# wordClock.net
KiCad netlist of a schematic drawn in EAGLE
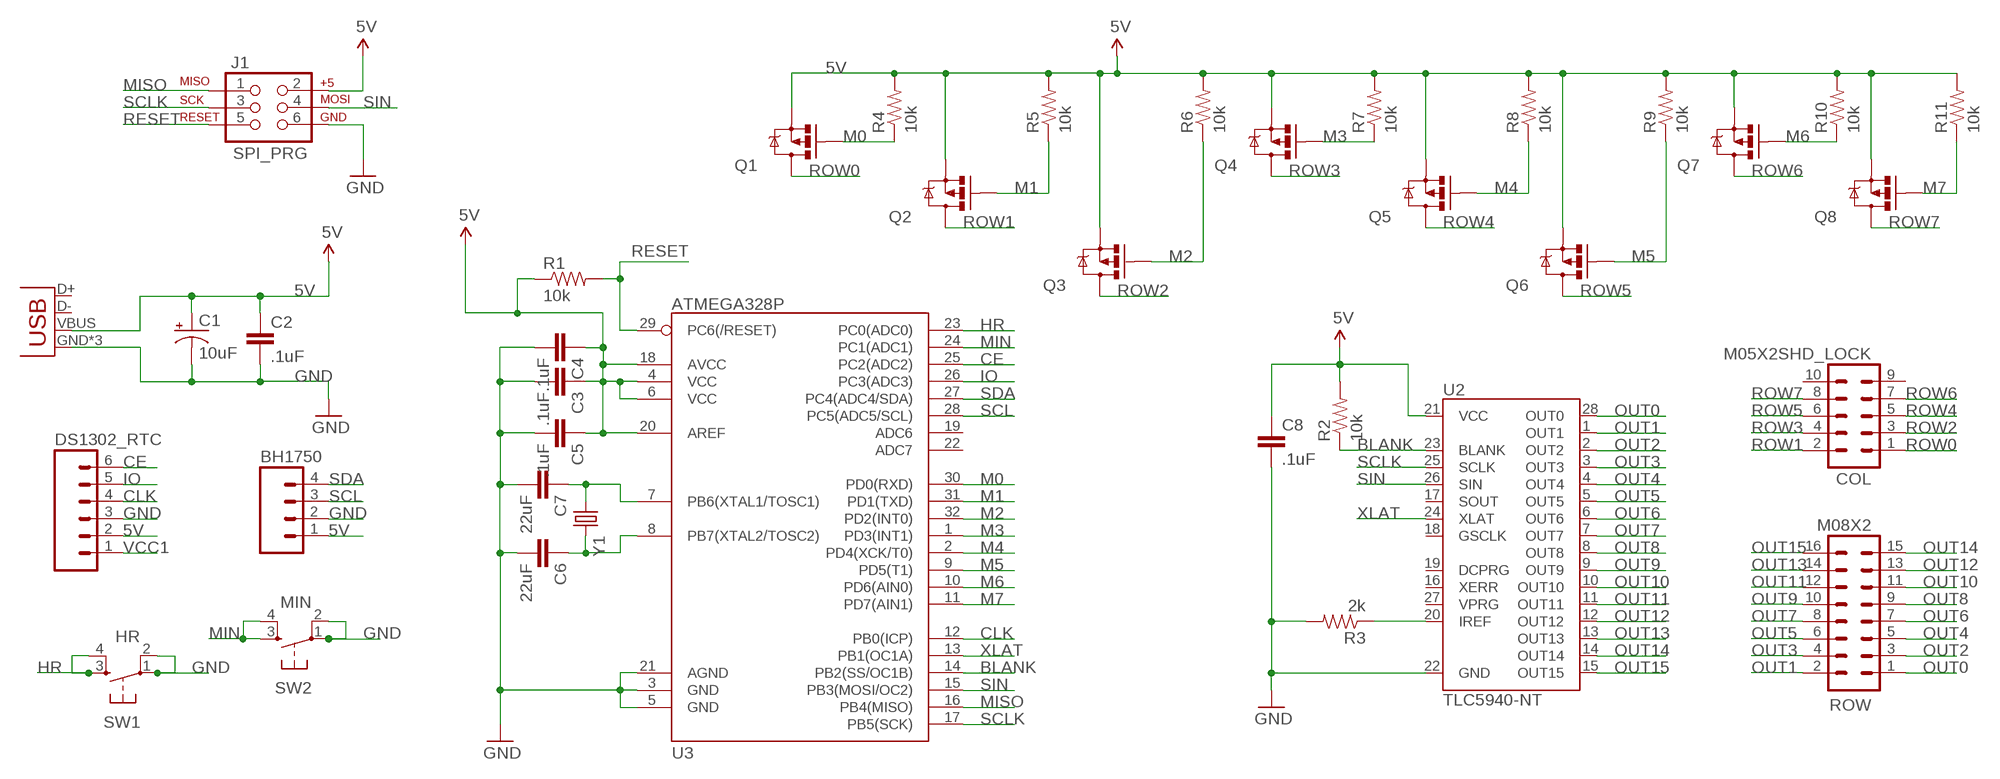
[diagram p0: schematic, sheet 1]

(export (version "E")
  (design (tool "Eeschema 10.0.6"))
  (components
    (comp (ref "BH1750")
      (value "M04LOCK")
      (footprint "eagle-import:1X04_LOCK")
      (libsource (lib "eagle-import") (part "M04LOCK"))
    )
    (comp (ref "C1")
      (value "10uF")
      (footprint "eagle-import:PANASONIC_D")
      (libsource (lib "eagle-import") (part "CAP_POLD"))
    )
    (comp (ref "C2")
      (value ".1uF")
      (footprint "eagle-import:0805")
      (libsource (lib "eagle-import") (part "CAP0805"))
    )
    (comp (ref "C3")
      (value ".1uF")
      (footprint "eagle-import:0805")
      (libsource (lib "eagle-import") (part "CAP0805"))
    )
    (comp (ref "C4")
      (value ".1uF")
      (footprint "eagle-import:0805")
      (libsource (lib "eagle-import") (part "CAP0805"))
    )
    (comp (ref "C5")
      (value ".1uF")
      (footprint "eagle-import:0805")
      (libsource (lib "eagle-import") (part "CAP0805"))
    )
    (comp (ref "C6")
      (value "22uF")
      (footprint "eagle-import:0805")
      (libsource (lib "eagle-import") (part "CAP0805"))
    )
    (comp (ref "C7")
      (value "22uF")
      (footprint "eagle-import:0805")
      (libsource (lib "eagle-import") (part "CAP0805"))
    )
    (comp (ref "C8")
      (value ".1uF")
      (footprint "eagle-import:0805")
      (libsource (lib "eagle-import") (part "CAP0805"))
    )
    (comp (ref "COL")
      (value "M05X2SHD_LOCK")
      (footprint "eagle-import:2X5-SHROUDED_LOCK")
      (libsource (lib "eagle-import") (part "M05X2SHD_LOCK"))
    )
    (comp (ref "DS1302_RTC")
      (value "M06FEMALE_LOCK")
      (footprint "eagle-import:1X06_FEMALE_LOCK.010")
      (libsource (lib "eagle-import") (part "M06FEMALE_LOCK"))
    )
    (comp (ref "J1")
      (value "SPI_PRG")
      (footprint "eagle-import:2X3_LOCK")
      (libsource (lib "eagle-import") (part "AVR_SPI_PRG_62X3_LOCK"))
    )
    (comp (ref "JP1")
      (value "USB-MICROB")
      (footprint "eagle-import:USB-MICROB")
      (libsource (lib "eagle-import") (part "USB-MICROB"))
    )
    (comp (ref "Q1")
      (value "MOSFET-PCHANNELSMD")
      (footprint "eagle-import:SOT23-3")
      (libsource (lib "eagle-import") (part "MOSFET-PCHANNELSMD"))
    )
    (comp (ref "Q2")
      (value "MOSFET-PCHANNELSMD")
      (footprint "eagle-import:SOT23-3")
      (libsource (lib "eagle-import") (part "MOSFET-PCHANNELSMD"))
    )
    (comp (ref "Q3")
      (value "MOSFET-PCHANNELSMD")
      (footprint "eagle-import:SOT23-3")
      (libsource (lib "eagle-import") (part "MOSFET-PCHANNELSMD"))
    )
    (comp (ref "Q4")
      (value "MOSFET-PCHANNELSMD")
      (footprint "eagle-import:SOT23-3")
      (libsource (lib "eagle-import") (part "MOSFET-PCHANNELSMD"))
    )
    (comp (ref "Q5")
      (value "MOSFET-PCHANNELSMD")
      (footprint "eagle-import:SOT23-3")
      (libsource (lib "eagle-import") (part "MOSFET-PCHANNELSMD"))
    )
    (comp (ref "Q6")
      (value "MOSFET-PCHANNELSMD")
      (footprint "eagle-import:SOT23-3")
      (libsource (lib "eagle-import") (part "MOSFET-PCHANNELSMD"))
    )
    (comp (ref "Q7")
      (value "MOSFET-PCHANNELSMD")
      (footprint "eagle-import:SOT23-3")
      (libsource (lib "eagle-import") (part "MOSFET-PCHANNELSMD"))
    )
    (comp (ref "Q8")
      (value "MOSFET-PCHANNELSMD")
      (footprint "eagle-import:SOT23-3")
      (libsource (lib "eagle-import") (part "MOSFET-PCHANNELSMD"))
    )
    (comp (ref "R1")
      (value "10k")
      (footprint "eagle-import:0805")
      (libsource (lib "eagle-import") (part "RESISTOR0805-RES"))
    )
    (comp (ref "R2")
      (value "10k")
      (footprint "eagle-import:0805")
      (libsource (lib "eagle-import") (part "RESISTOR0805-RES"))
    )
    (comp (ref "R3")
      (value "2k")
      (footprint "eagle-import:0805")
      (libsource (lib "eagle-import") (part "RESISTOR0805-RES"))
    )
    (comp (ref "R4")
      (value "10k")
      (footprint "eagle-import:0805")
      (libsource (lib "eagle-import") (part "RESISTOR0805-RES"))
    )
    (comp (ref "R5")
      (value "10k")
      (footprint "eagle-import:0805")
      (libsource (lib "eagle-import") (part "RESISTOR0805-RES"))
    )
    (comp (ref "R6")
      (value "10k")
      (footprint "eagle-import:0805")
      (libsource (lib "eagle-import") (part "RESISTOR0805-RES"))
    )
    (comp (ref "R7")
      (value "10k")
      (footprint "eagle-import:0805")
      (libsource (lib "eagle-import") (part "RESISTOR0805-RES"))
    )
    (comp (ref "R8")
      (value "10k")
      (footprint "eagle-import:0805")
      (libsource (lib "eagle-import") (part "RESISTOR0805-RES"))
    )
    (comp (ref "R9")
      (value "10k")
      (footprint "eagle-import:0805")
      (libsource (lib "eagle-import") (part "RESISTOR0805-RES"))
    )
    (comp (ref "R10")
      (value "10k")
      (footprint "eagle-import:0805")
      (libsource (lib "eagle-import") (part "RESISTOR0805-RES"))
    )
    (comp (ref "R11")
      (value "10k")
      (footprint "eagle-import:0805")
      (libsource (lib "eagle-import") (part "RESISTOR0805-RES"))
    )
    (comp (ref "ROW")
      (value "M08X2")
      (footprint "eagle-import:2X8")
      (libsource (lib "eagle-import") (part "M08X2"))
    )
    (comp (ref "SW1")
      (value "HR")
      (footprint "eagle-import:TACTILE-PTH")
      (libsource (lib "eagle-import") (part "TAC_SWITCHPTH"))
    )
    (comp (ref "SW2")
      (value "MIN")
      (footprint "eagle-import:TACTILE-PTH")
      (libsource (lib "eagle-import") (part "TAC_SWITCHPTH"))
    )
    (comp (ref "U2")
      (value "TLC5940-NT")
      (footprint "eagle-import:DIL28-3")
      (libsource (lib "eagle-import") (part "TLC5940-NT"))
    )
    (comp (ref "U3")
      (value "ATMEGA328P")
      (footprint "eagle-import:TQFP32-08")
      (libsource (lib "eagle-import") (part "ATMEGA328_SMT"))
    )
    (comp (ref "Y1")
      (value "CRYSTALHC49UV")
      (footprint "eagle-import:HC49U-V")
      (libsource (lib "eagle-import") (part "CRYSTALHC49UV"))
    )
  )
  (nets
    (net (code "1") (name "/BLANK") (class "Default")
      (node (ref "R2") (pin "1") (pinfunction "1_1") (pintype "passive"))
      (node (ref "U2") (pin "23") (pinfunction "BLANK_23") (pintype "bidirectional"))
      (node (ref "U3") (pin "14") (pinfunction "PB2(SS/OC1B)_14") (pintype "bidirectional"))
    )
    (net (code "2") (name "/CE") (class "Default")
      (node (ref "DS1302_RTC") (pin "6") (pinfunction "6_6") (pintype "passive"))
      (node (ref "U3") (pin "25") (pinfunction "PC2(ADC2)_25") (pintype "bidirectional"))
    )
    (net (code "3") (name "/CLK") (class "Default")
      (node (ref "DS1302_RTC") (pin "4") (pinfunction "4_4") (pintype "passive"))
      (node (ref "U3") (pin "12") (pinfunction "PB0(ICP)_12") (pintype "bidirectional"))
    )
    (net (code "4") (name "/HR") (class "Default")
      (node (ref "SW1") (pin "3") (pinfunction "3_3") (pintype "passive"))
      (node (ref "SW1") (pin "4") (pinfunction "4_4") (pintype "passive"))
      (node (ref "U3") (pin "23") (pinfunction "PC0(ADC0)_23") (pintype "bidirectional"))
    )
    (net (code "5") (name "/IO") (class "Default")
      (node (ref "DS1302_RTC") (pin "5") (pinfunction "5_5") (pintype "passive"))
      (node (ref "U3") (pin "26") (pinfunction "PC3(ADC3)_26") (pintype "bidirectional"))
    )
    (net (code "6") (name "/M0") (class "Default")
      (node (ref "Q1") (pin "1") (pinfunction "G_1") (pintype "passive"))
      (node (ref "R4") (pin "1") (pinfunction "1_1") (pintype "passive"))
      (node (ref "U3") (pin "30") (pinfunction "PD0(RXD)_30") (pintype "bidirectional"))
    )
    (net (code "7") (name "/M1") (class "Default")
      (node (ref "Q2") (pin "1") (pinfunction "G_1") (pintype "passive"))
      (node (ref "R5") (pin "1") (pinfunction "1_1") (pintype "passive"))
      (node (ref "U3") (pin "31") (pinfunction "PD1(TXD)_31") (pintype "bidirectional"))
    )
    (net (code "8") (name "/M2") (class "Default")
      (node (ref "Q3") (pin "1") (pinfunction "G_1") (pintype "passive"))
      (node (ref "R6") (pin "1") (pinfunction "1_1") (pintype "passive"))
      (node (ref "U3") (pin "32") (pinfunction "PD2(INT0)_32") (pintype "bidirectional"))
    )
    (net (code "9") (name "/M3") (class "Default")
      (node (ref "Q4") (pin "1") (pinfunction "G_1") (pintype "passive"))
      (node (ref "R7") (pin "1") (pinfunction "1_1") (pintype "passive"))
      (node (ref "U3") (pin "1") (pinfunction "PD3(INT1)_1") (pintype "bidirectional"))
    )
    (net (code "10") (name "/M4") (class "Default")
      (node (ref "Q5") (pin "1") (pinfunction "G_1") (pintype "passive"))
      (node (ref "R8") (pin "1") (pinfunction "1_1") (pintype "passive"))
      (node (ref "U3") (pin "2") (pinfunction "PD4(XCK/T0)_2") (pintype "bidirectional"))
    )
    (net (code "11") (name "/M5") (class "Default")
      (node (ref "Q6") (pin "1") (pinfunction "G_1") (pintype "passive"))
      (node (ref "R9") (pin "1") (pinfunction "1_1") (pintype "passive"))
      (node (ref "U3") (pin "9") (pinfunction "PD5(T1)_9") (pintype "bidirectional"))
    )
    (net (code "12") (name "/M6") (class "Default")
      (node (ref "Q7") (pin "1") (pinfunction "G_1") (pintype "passive"))
      (node (ref "R10") (pin "1") (pinfunction "1_1") (pintype "passive"))
      (node (ref "U3") (pin "10") (pinfunction "PD6(AIN0)_10") (pintype "bidirectional"))
    )
    (net (code "13") (name "/M7") (class "Default")
      (node (ref "Q8") (pin "1") (pinfunction "G_1") (pintype "passive"))
      (node (ref "R11") (pin "1") (pinfunction "1_1") (pintype "passive"))
      (node (ref "U3") (pin "11") (pinfunction "PD7(AIN1)_11") (pintype "bidirectional"))
    )
    (net (code "14") (name "/MIN") (class "Default")
      (node (ref "SW2") (pin "3") (pinfunction "3_3") (pintype "passive"))
      (node (ref "SW2") (pin "4") (pinfunction "4_4") (pintype "passive"))
      (node (ref "U3") (pin "24") (pinfunction "PC1(ADC1)_24") (pintype "bidirectional"))
    )
    (net (code "15") (name "/MISO") (class "Default")
      (node (ref "J1") (pin "1") (pinfunction "1_1") (pintype "passive"))
      (node (ref "U3") (pin "16") (pinfunction "PB4(MISO)_16") (pintype "bidirectional"))
    )
    (net (code "16") (name "/OUT0") (class "Default")
      (node (ref "ROW") (pin "1") (pinfunction "1_1") (pintype "passive"))
      (node (ref "U2") (pin "28") (pinfunction "OUT0_28") (pintype "bidirectional"))
    )
    (net (code "17") (name "/OUT1") (class "Default")
      (node (ref "ROW") (pin "2") (pinfunction "2_2") (pintype "passive"))
      (node (ref "U2") (pin "1") (pinfunction "OUT1_1") (pintype "bidirectional"))
    )
    (net (code "18") (name "/OUT2") (class "Default")
      (node (ref "ROW") (pin "3") (pinfunction "3_3") (pintype "passive"))
      (node (ref "U2") (pin "2") (pinfunction "OUT2_2") (pintype "bidirectional"))
    )
    (net (code "19") (name "/OUT3") (class "Default")
      (node (ref "ROW") (pin "4") (pinfunction "4_4") (pintype "passive"))
      (node (ref "U2") (pin "3") (pinfunction "OUT3_3") (pintype "bidirectional"))
    )
    (net (code "20") (name "/OUT4") (class "Default")
      (node (ref "ROW") (pin "5") (pinfunction "5_5") (pintype "passive"))
      (node (ref "U2") (pin "4") (pinfunction "OUT4_4") (pintype "bidirectional"))
    )
    (net (code "21") (name "/OUT5") (class "Default")
      (node (ref "ROW") (pin "6") (pinfunction "6_6") (pintype "passive"))
      (node (ref "U2") (pin "5") (pinfunction "OUT5_5") (pintype "bidirectional"))
    )
    (net (code "22") (name "/OUT6") (class "Default")
      (node (ref "ROW") (pin "7") (pinfunction "7_7") (pintype "passive"))
      (node (ref "U2") (pin "6") (pinfunction "OUT6_6") (pintype "bidirectional"))
    )
    (net (code "23") (name "/OUT7") (class "Default")
      (node (ref "ROW") (pin "8") (pinfunction "8_8") (pintype "passive"))
      (node (ref "U2") (pin "7") (pinfunction "OUT7_7") (pintype "bidirectional"))
    )
    (net (code "24") (name "/OUT8") (class "Default")
      (node (ref "ROW") (pin "9") (pinfunction "9_9") (pintype "passive"))
      (node (ref "U2") (pin "8") (pinfunction "OUT8_8") (pintype "bidirectional"))
    )
    (net (code "25") (name "/OUT9") (class "Default")
      (node (ref "ROW") (pin "10") (pinfunction "10_10") (pintype "passive"))
      (node (ref "U2") (pin "9") (pinfunction "OUT9_9") (pintype "bidirectional"))
    )
    (net (code "26") (name "/OUT10") (class "Default")
      (node (ref "ROW") (pin "11") (pinfunction "11_11") (pintype "passive"))
      (node (ref "U2") (pin "10") (pinfunction "OUT10_10") (pintype "bidirectional"))
    )
    (net (code "27") (name "/OUT11") (class "Default")
      (node (ref "ROW") (pin "12") (pinfunction "12_12") (pintype "passive"))
      (node (ref "U2") (pin "11") (pinfunction "OUT11_11") (pintype "bidirectional"))
    )
    (net (code "28") (name "/OUT12") (class "Default")
      (node (ref "ROW") (pin "13") (pinfunction "13_13") (pintype "passive"))
      (node (ref "U2") (pin "12") (pinfunction "OUT12_12") (pintype "bidirectional"))
    )
    (net (code "29") (name "/OUT13") (class "Default")
      (node (ref "ROW") (pin "14") (pinfunction "14_14") (pintype "passive"))
      (node (ref "U2") (pin "13") (pinfunction "OUT13_13") (pintype "bidirectional"))
    )
    (net (code "30") (name "/OUT14") (class "Default")
      (node (ref "ROW") (pin "15") (pinfunction "15_15") (pintype "passive"))
      (node (ref "U2") (pin "14") (pinfunction "OUT14_14") (pintype "bidirectional"))
    )
    (net (code "31") (name "/OUT15") (class "Default")
      (node (ref "ROW") (pin "16") (pinfunction "16_16") (pintype "passive"))
      (node (ref "U2") (pin "15") (pinfunction "OUT15_15") (pintype "bidirectional"))
    )
    (net (code "32") (name "/RESET") (class "Default")
      (node (ref "J1") (pin "5") (pinfunction "5_5") (pintype "passive"))
      (node (ref "R1") (pin "2") (pinfunction "2_2") (pintype "passive"))
      (node (ref "U3") (pin "29") (pinfunction "PC6(/RESET)_29") (pintype "bidirectional"))
    )
    (net (code "33") (name "/ROW0") (class "Default")
      (node (ref "COL") (pin "1") (pinfunction "1_1") (pintype "passive"))
      (node (ref "Q1") (pin "3") (pinfunction "D_3") (pintype "passive"))
    )
    (net (code "34") (name "/ROW1") (class "Default")
      (node (ref "COL") (pin "2") (pinfunction "2_2") (pintype "passive"))
      (node (ref "Q2") (pin "3") (pinfunction "D_3") (pintype "passive"))
    )
    (net (code "35") (name "/ROW2") (class "Default")
      (node (ref "COL") (pin "3") (pinfunction "3_3") (pintype "passive"))
      (node (ref "Q3") (pin "3") (pinfunction "D_3") (pintype "passive"))
    )
    (net (code "36") (name "/ROW3") (class "Default")
      (node (ref "COL") (pin "4") (pinfunction "4_4") (pintype "passive"))
      (node (ref "Q4") (pin "3") (pinfunction "D_3") (pintype "passive"))
    )
    (net (code "37") (name "/ROW4") (class "Default")
      (node (ref "COL") (pin "5") (pinfunction "5_5") (pintype "passive"))
      (node (ref "Q5") (pin "3") (pinfunction "D_3") (pintype "passive"))
    )
    (net (code "38") (name "/ROW5") (class "Default")
      (node (ref "COL") (pin "6") (pinfunction "6_6") (pintype "passive"))
      (node (ref "Q6") (pin "3") (pinfunction "D_3") (pintype "passive"))
    )
    (net (code "39") (name "/ROW6") (class "Default")
      (node (ref "COL") (pin "7") (pinfunction "7_7") (pintype "passive"))
      (node (ref "Q7") (pin "3") (pinfunction "D_3") (pintype "passive"))
    )
    (net (code "40") (name "/ROW7") (class "Default")
      (node (ref "COL") (pin "8") (pinfunction "8_8") (pintype "passive"))
      (node (ref "Q8") (pin "3") (pinfunction "D_3") (pintype "passive"))
    )
    (net (code "41") (name "/SCL") (class "Default")
      (node (ref "BH1750") (pin "3") (pinfunction "3_3") (pintype "passive"))
      (node (ref "U3") (pin "28") (pinfunction "PC5(ADC5/SCL)_28") (pintype "bidirectional"))
    )
    (net (code "42") (name "/SCLK") (class "Default")
      (node (ref "J1") (pin "3") (pinfunction "3_3") (pintype "passive"))
      (node (ref "U2") (pin "25") (pinfunction "SCLK_25") (pintype "bidirectional"))
      (node (ref "U3") (pin "17") (pinfunction "PB5(SCK)_17") (pintype "bidirectional"))
    )
    (net (code "43") (name "/SDA") (class "Default")
      (node (ref "BH1750") (pin "4") (pinfunction "4_4") (pintype "passive"))
      (node (ref "U3") (pin "27") (pinfunction "PC4(ADC4/SDA)_27") (pintype "bidirectional"))
    )
    (net (code "44") (name "/SIN") (class "Default")
      (node (ref "J1") (pin "4") (pinfunction "4_4") (pintype "passive"))
      (node (ref "U2") (pin "26") (pinfunction "SIN_26") (pintype "bidirectional"))
      (node (ref "U3") (pin "15") (pinfunction "PB3(MOSI/OC2)_15") (pintype "bidirectional"))
    )
    (net (code "45") (name "/VCC1") (class "Default")
      (node (ref "DS1302_RTC") (pin "1") (pinfunction "1_1") (pintype "passive"))
    )
    (net (code "46") (name "/XLAT") (class "Default")
      (node (ref "U2") (pin "24") (pinfunction "XLAT_24") (pintype "bidirectional"))
      (node (ref "U3") (pin "13") (pinfunction "PB1(OC1A)_13") (pintype "bidirectional"))
    )
    (net (code "47") (name "5V") (class "Default")
      (node (ref "BH1750") (pin "1") (pinfunction "1_1") (pintype "passive"))
      (node (ref "C1") (pin "+") (pinfunction "+_+") (pintype "passive"))
      (node (ref "C2") (pin "1") (pinfunction "1_1") (pintype "passive"))
      (node (ref "C3") (pin "1") (pinfunction "1_1") (pintype "passive"))
      (node (ref "C4") (pin "1") (pinfunction "1_1") (pintype "passive"))
      (node (ref "C5") (pin "1") (pinfunction "1_1") (pintype "passive"))
      (node (ref "C8") (pin "1") (pinfunction "1_1") (pintype "passive"))
      (node (ref "DS1302_RTC") (pin "2") (pinfunction "2_2") (pintype "passive"))
      (node (ref "J1") (pin "2") (pinfunction "2_2") (pintype "passive"))
      (node (ref "JP1") (pin "VBUS") (pinfunction "VBUS_VBUS") (pintype "bidirectional"))
      (node (ref "Q1") (pin "2") (pinfunction "S_2") (pintype "passive"))
      (node (ref "Q2") (pin "2") (pinfunction "S_2") (pintype "passive"))
      (node (ref "Q3") (pin "2") (pinfunction "S_2") (pintype "passive"))
      (node (ref "Q4") (pin "2") (pinfunction "S_2") (pintype "passive"))
      (node (ref "Q5") (pin "2") (pinfunction "S_2") (pintype "passive"))
      (node (ref "Q6") (pin "2") (pinfunction "S_2") (pintype "passive"))
      (node (ref "Q7") (pin "2") (pinfunction "S_2") (pintype "passive"))
      (node (ref "Q8") (pin "2") (pinfunction "S_2") (pintype "passive"))
      (node (ref "R1") (pin "1") (pinfunction "1_1") (pintype "passive"))
      (node (ref "R10") (pin "2") (pinfunction "2_2") (pintype "passive"))
      (node (ref "R11") (pin "2") (pinfunction "2_2") (pintype "passive"))
      (node (ref "R2") (pin "2") (pinfunction "2_2") (pintype "passive"))
      (node (ref "R4") (pin "2") (pinfunction "2_2") (pintype "passive"))
      (node (ref "R5") (pin "2") (pinfunction "2_2") (pintype "passive"))
      (node (ref "R6") (pin "2") (pinfunction "2_2") (pintype "passive"))
      (node (ref "R7") (pin "2") (pinfunction "2_2") (pintype "passive"))
      (node (ref "R8") (pin "2") (pinfunction "2_2") (pintype "passive"))
      (node (ref "R9") (pin "2") (pinfunction "2_2") (pintype "passive"))
      (node (ref "U2") (pin "21") (pinfunction "VCC_21") (pintype "bidirectional"))
      (node (ref "U3") (pin "18") (pinfunction "AVCC_18") (pintype "bidirectional"))
      (node (ref "U3") (pin "20") (pinfunction "AREF_20") (pintype "bidirectional"))
      (node (ref "U3") (pin "4") (pinfunction "VCC_4") (pintype "bidirectional"))
      (node (ref "U3") (pin "6") (pinfunction "VCC_6") (pintype "bidirectional"))
    )
    (net (code "48") (name "GND") (class "Default")
      (node (ref "BH1750") (pin "2") (pinfunction "2_2") (pintype "passive"))
      (node (ref "C1") (pin "-") (pinfunction "-_-") (pintype "passive"))
      (node (ref "C2") (pin "2") (pinfunction "2_2") (pintype "passive"))
      (node (ref "C3") (pin "2") (pinfunction "2_2") (pintype "passive"))
      (node (ref "C4") (pin "2") (pinfunction "2_2") (pintype "passive"))
      (node (ref "C5") (pin "2") (pinfunction "2_2") (pintype "passive"))
      (node (ref "C6") (pin "2") (pinfunction "2_2") (pintype "passive"))
      (node (ref "C7") (pin "2") (pinfunction "2_2") (pintype "passive"))
      (node (ref "C8") (pin "2") (pinfunction "2_2") (pintype "passive"))
      (node (ref "DS1302_RTC") (pin "3") (pinfunction "3_3") (pintype "passive"))
      (node (ref "J1") (pin "6") (pinfunction "6_6") (pintype "passive"))
      (node (ref "JP1") (pin "GND") (pinfunction "GND_GND") (pintype "bidirectional"))
      (node (ref "JP1") (pin "MT1") (pinfunction "GND_MT1") (pintype "bidirectional"))
      (node (ref "JP1") (pin "MT2") (pinfunction "GND_MT2") (pintype "bidirectional"))
      (node (ref "R3") (pin "2") (pinfunction "2_2") (pintype "passive"))
      (node (ref "SW1") (pin "1") (pinfunction "1_1") (pintype "passive"))
      (node (ref "SW1") (pin "2") (pinfunction "2_2") (pintype "passive"))
      (node (ref "SW2") (pin "1") (pinfunction "1_1") (pintype "passive"))
      (node (ref "SW2") (pin "2") (pinfunction "2_2") (pintype "passive"))
      (node (ref "U2") (pin "22") (pinfunction "GND_22") (pintype "bidirectional"))
      (node (ref "U3") (pin "21") (pinfunction "AGND_21") (pintype "bidirectional"))
      (node (ref "U3") (pin "3") (pinfunction "GND_3") (pintype "bidirectional"))
      (node (ref "U3") (pin "5") (pinfunction "GND_5") (pintype "bidirectional"))
    )
    (net (code "49") (name "Net-(U2-IREF)") (class "Default")
      (node (ref "R3") (pin "1") (pinfunction "1_1") (pintype "passive"))
      (node (ref "U2") (pin "20") (pinfunction "IREF_20") (pintype "bidirectional"))
    )
    (net (code "50") (name "Net-(U3-PB6(XTAL1{slash}TOSC1))") (class "Default")
      (node (ref "C7") (pin "1") (pinfunction "1_1") (pintype "passive"))
      (node (ref "U3") (pin "7") (pinfunction "PB6(XTAL1/TOSC1)_7") (pintype "bidirectional"))
      (node (ref "Y1") (pin "1") (pinfunction "1_1") (pintype "passive"))
    )
    (net (code "51") (name "Net-(U3-PB7(XTAL2{slash}TOSC2))") (class "Default")
      (node (ref "C6") (pin "1") (pinfunction "1_1") (pintype "passive"))
      (node (ref "U3") (pin "8") (pinfunction "PB7(XTAL2/TOSC2)_8") (pintype "bidirectional"))
      (node (ref "Y1") (pin "2") (pinfunction "2_2") (pintype "passive"))
    )
    (net (code "52") (name "unconnected-(COL-Pad9)") (class "Default")
      (node (ref "COL") (pin "9") (pinfunction "9_9") (pintype "passive"))
    )
    (net (code "53") (name "unconnected-(COL-Pad10)") (class "Default")
      (node (ref "COL") (pin "10") (pinfunction "10_10") (pintype "passive"))
    )
    (net (code "54") (name "unconnected-(JP1-PadD+)") (class "Default")
      (node (ref "JP1") (pin "D+") (pinfunction "D+_D+") (pintype "bidirectional"))
    )
    (net (code "55") (name "unconnected-(JP1-PadD-)") (class "Default")
      (node (ref "JP1") (pin "D-") (pinfunction "D-_D-") (pintype "bidirectional"))
    )
    (net (code "56") (name "unconnected-(U2-DCPRG-Pad19)") (class "Default")
      (node (ref "U2") (pin "19") (pinfunction "DCPRG_19") (pintype "bidirectional"))
    )
    (net (code "57") (name "unconnected-(U2-GSCLK-Pad18)") (class "Default")
      (node (ref "U2") (pin "18") (pinfunction "GSCLK_18") (pintype "bidirectional"))
    )
    (net (code "58") (name "unconnected-(U2-SOUT-Pad17)") (class "Default")
      (node (ref "U2") (pin "17") (pinfunction "SOUT_17") (pintype "bidirectional"))
    )
    (net (code "59") (name "unconnected-(U2-VPRG-Pad27)") (class "Default")
      (node (ref "U2") (pin "27") (pinfunction "VPRG_27") (pintype "bidirectional"))
    )
    (net (code "60") (name "unconnected-(U2-XERR-Pad16)") (class "Default")
      (node (ref "U2") (pin "16") (pinfunction "XERR_16") (pintype "bidirectional"))
    )
    (net (code "61") (name "unconnected-(U3-ADC6-Pad19)") (class "Default")
      (node (ref "U3") (pin "19") (pinfunction "ADC6_19") (pintype "bidirectional"))
    )
    (net (code "62") (name "unconnected-(U3-ADC7-Pad22)") (class "Default")
      (node (ref "U3") (pin "22") (pinfunction "ADC7_22") (pintype "bidirectional"))
    )
  )
)
